# OSD.net
KiCad netlist of a schematic drawn in Altium Designer
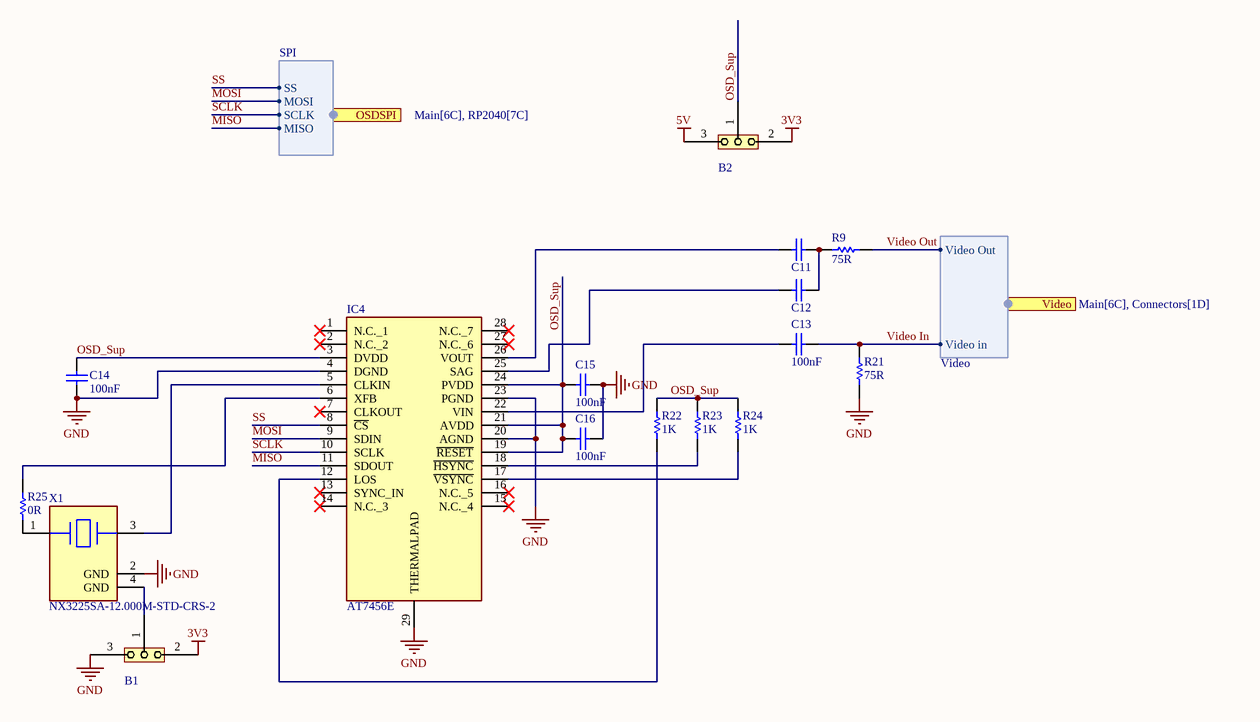
[diagram p0: OSD.SchDoc]

(export (version "E")
  (design (tool "Eeschema 10.0.6"))
  (components
    (comp (ref "B1")
      (value "0402 Solder Bridge")
      (footprint "Custom Components:0402 triple Solderbridge")
      (libsource (lib "Custom Components") (part "0402 Solder Bridge"))
    )
    (comp (ref "B2")
      (value "0402 Solder Bridge")
      (footprint "Custom Components:0402 triple Solderbridge")
      (libsource (lib "Custom Components") (part "0402 Solder Bridge"))
    )
    (comp (ref "C11")
      (value "10µF")
      (footprint "WCAP-CSGP_0603_L1.6W0.8H0.8_Reflow")
      (description "WCAP-CSGP Multilayer Ceramic Chip Capacitor, General Purpose, size 0603, X5R, 10µF, 25VDC")
      (fields
        (field (name "MANUFACTURER PART NUMBER") "885012106031")
        (field (name "MANUFACTURER") "Wurth Elektronik")
      )
      (libsource (lib "Altium_WCAP-CSGP (rev22f)") (part "885012106031"))
    )
    (comp (ref "C12")
      (value "10µF")
      (footprint "WCAP-CSGP_0603_L1.6W0.8H0.8_Reflow")
      (description "WCAP-CSGP Multilayer Ceramic Chip Capacitor, General Purpose, size 0603, X5R, 10µF, 25VDC")
      (fields
        (field (name "MANUFACTURER PART NUMBER") "885012106031")
        (field (name "MANUFACTURER") "Wurth Elektronik")
      )
      (libsource (lib "Altium_WCAP-CSGP (rev22f)") (part "885012106031"))
    )
    (comp (ref "C13")
      (value "100nF")
      (footprint "0402 cap")
      (libsource (lib "Custom Components") (part "Capacitor 0402 100nF"))
    )
    (comp (ref "C14")
      (value "100nF")
      (footprint "0402 cap")
      (libsource (lib "Custom Components") (part "Capacitor 0402 100nF"))
    )
    (comp (ref "C15")
      (value "100nF")
      (footprint "0402 cap")
      (libsource (lib "Custom Components") (part "Capacitor 0402 100nF"))
    )
    (comp (ref "C16")
      (value "100nF")
      (footprint "0402 cap")
      (libsource (lib "Custom Components") (part "Capacitor 0402 100nF"))
    )
    (comp (ref "IC4")
      (value "AT7456E")
      (footprint "SOP65P640X120-29N")
      (description "Integrated Circuit")
      (libsource (lib "Custom Components") (part "AT7456E"))
    )
    (comp (ref "R9")
      (value "75R")
      (footprint "Custom Components:0402 resistor")
      (libsource (lib "Custom Components") (part "Resistor 0402 1K"))
    )
    (comp (ref "R21")
      (value "75R")
      (footprint "Custom Components:0402 resistor")
      (libsource (lib "Custom Components") (part "Resistor 0402 1K"))
    )
    (comp (ref "R22")
      (value "1K")
      (footprint "Custom Components:0402 resistor")
      (libsource (lib "Custom Components") (part "Resistor 0402 1K"))
    )
    (comp (ref "R23")
      (value "1K")
      (footprint "Custom Components:0402 resistor")
      (libsource (lib "Custom Components") (part "Resistor 0402 1K"))
    )
    (comp (ref "R24")
      (value "1K")
      (footprint "Custom Components:0402 resistor")
      (libsource (lib "Custom Components") (part "Resistor 0402 1K"))
    )
    (comp (ref "R25")
      (value "0R")
      (footprint "Custom Components:0402 resistor")
      (libsource (lib "Custom Components") (part "Resistor 0402 1K"))
    )
    (comp (ref "X1")
      (value "NX3225SA-12.000M-STD-CRS-2")
      (footprint "FP-NX3225SA-MFG")
      (libsource (lib "Altium Content Vault") (part "48e526d86b7f2615d98721063c72f49"))
    )
  )
  (nets
    (net (code "3") (name "/MISO") (class "Default")
      (node (ref "IC4") (pin "11") (pinfunction "SDOUT_11") (pintype "passive"))
    )
    (net (code "4") (name "/MOSI") (class "Default")
      (node (ref "IC4") (pin "9") (pinfunction "SDIN_9") (pintype "passive"))
    )
    (net (code "5") (name "/OSD_Sup") (class "Default")
      (node (ref "B2") (pin "1") (pinfunction "1_1") (pintype "passive"))
      (node (ref "C14") (pin "2") (pinfunction "2_2") (pintype "passive"))
      (node (ref "C15") (pin "1") (pinfunction "1_1") (pintype "passive"))
      (node (ref "C16") (pin "1") (pinfunction "1_1") (pintype "passive"))
      (node (ref "IC4") (pin "19") (pinfunction "~{RESET}_19") (pintype "passive"))
      (node (ref "IC4") (pin "21") (pinfunction "AVDD_21") (pintype "passive"))
      (node (ref "IC4") (pin "24") (pinfunction "PVDD_24") (pintype "passive"))
      (node (ref "IC4") (pin "3") (pinfunction "DVDD_3") (pintype "passive"))
      (node (ref "R22") (pin "2") (pinfunction "2_2") (pintype "passive"))
      (node (ref "R23") (pin "2") (pinfunction "2_2") (pintype "passive"))
      (node (ref "R24") (pin "2") (pinfunction "2_2") (pintype "passive"))
    )
    (net (code "6") (name "/SCLK") (class "Default")
      (node (ref "IC4") (pin "10") (pinfunction "SCLK_10") (pintype "passive"))
    )
    (net (code "7") (name "/SS") (class "Default")
      (node (ref "IC4") (pin "8") (pinfunction "~{CS}_8") (pintype "passive"))
    )
    (net (code "8") (name "/Video In") (class "Default")
      (node (ref "C13") (pin "2") (pinfunction "2_2") (pintype "passive"))
      (node (ref "R21") (pin "1") (pinfunction "1_1") (pintype "passive"))
    )
    (net (code "9") (name "/Video Out") (class "Default")
      (node (ref "R9") (pin "1") (pinfunction "1_1") (pintype "passive"))
    )
    (net (code "12") (name "3V3") (class "Default")
      (node (ref "B1") (pin "2") (pinfunction "2_2") (pintype "passive"))
      (node (ref "B2") (pin "2") (pinfunction "2_2") (pintype "passive"))
    )
    (net (code "13") (name "5V") (class "Default")
      (node (ref "B2") (pin "3") (pinfunction "3_3") (pintype "passive"))
    )
    (net (code "14") (name "GND") (class "Default")
      (node (ref "B1") (pin "3") (pinfunction "3_3") (pintype "passive"))
      (node (ref "C14") (pin "1") (pinfunction "1_1") (pintype "passive"))
      (node (ref "C15") (pin "2") (pinfunction "2_2") (pintype "passive"))
      (node (ref "C16") (pin "2") (pinfunction "2_2") (pintype "passive"))
      (node (ref "IC4") (pin "20") (pinfunction "AGND_20") (pintype "passive"))
      (node (ref "IC4") (pin "23") (pinfunction "PGND_23") (pintype "passive"))
      (node (ref "IC4") (pin "29") (pinfunction "THERMALPAD_29") (pintype "passive"))
      (node (ref "IC4") (pin "4") (pinfunction "DGND_4") (pintype "passive"))
      (node (ref "R21") (pin "2") (pinfunction "2_2") (pintype "passive"))
      (node (ref "X1") (pin "2") (pinfunction "GND_2") (pintype "power_in"))
    )
    (net (code "15") (name "Net-(B1-Pad1)") (class "Default")
      (node (ref "B1") (pin "1") (pinfunction "1_1") (pintype "passive"))
      (node (ref "X1") (pin "4") (pinfunction "GND_4") (pintype "power_in"))
    )
    (net (code "16") (name "Net-(C11-Pad2)") (class "Default")
      (node (ref "C11") (pin "2") (pinfunction "2_2") (pintype "passive"))
      (node (ref "C12") (pin "2") (pinfunction "2_2") (pintype "passive"))
      (node (ref "R9") (pin "2") (pinfunction "2_2") (pintype "passive"))
    )
    (net (code "17") (name "Net-(IC4-CLKIN)") (class "Default")
      (node (ref "IC4") (pin "5") (pinfunction "CLKIN_5") (pintype "passive"))
      (node (ref "X1") (pin "3") (pinfunction "3_3") (pintype "passive"))
    )
    (net (code "18") (name "Net-(IC4-LOS)") (class "Default")
      (node (ref "IC4") (pin "12") (pinfunction "LOS_12") (pintype "passive"))
      (node (ref "R22") (pin "1") (pinfunction "1_1") (pintype "passive"))
    )
    (net (code "19") (name "Net-(IC4-SAG)") (class "Default")
      (node (ref "C12") (pin "1") (pinfunction "1_1") (pintype "passive"))
      (node (ref "IC4") (pin "25") (pinfunction "SAG_25") (pintype "passive"))
    )
    (net (code "20") (name "Net-(IC4-VIN)") (class "Default")
      (node (ref "C13") (pin "1") (pinfunction "1_1") (pintype "passive"))
      (node (ref "IC4") (pin "22") (pinfunction "VIN_22") (pintype "passive"))
    )
    (net (code "21") (name "Net-(IC4-VOUT)") (class "Default")
      (node (ref "C11") (pin "1") (pinfunction "1_1") (pintype "passive"))
      (node (ref "IC4") (pin "26") (pinfunction "VOUT_26") (pintype "passive"))
    )
    (net (code "22") (name "Net-(IC4-XFB)") (class "Default")
      (node (ref "IC4") (pin "6") (pinfunction "XFB_6") (pintype "passive"))
      (node (ref "R25") (pin "2") (pinfunction "2_2") (pintype "passive"))
    )
    (net (code "23") (name "Net-(IC4-~{HSYNC})") (class "Default")
      (node (ref "IC4") (pin "18") (pinfunction "~{HSYNC}_18") (pintype "passive"))
      (node (ref "R23") (pin "1") (pinfunction "1_1") (pintype "passive"))
    )
    (net (code "24") (name "Net-(IC4-~{VSYNC})") (class "Default")
      (node (ref "IC4") (pin "17") (pinfunction "~{VSYNC}_17") (pintype "passive"))
      (node (ref "R24") (pin "1") (pinfunction "1_1") (pintype "passive"))
    )
    (net (code "25") (name "Net-(R25-Pad1)") (class "Default")
      (node (ref "R25") (pin "1") (pinfunction "1_1") (pintype "passive"))
      (node (ref "X1") (pin "1") (pinfunction "1_1") (pintype "passive"))
    )
    (net (code "26") (name "unconnected-(IC4-CLKOUT-Pad7)") (class "Default")
      (node (ref "IC4") (pin "7") (pinfunction "CLKOUT_7") (pintype "passive+no_connect"))
    )
    (net (code "27") (name "unconnected-(IC4-N.C._1-Pad1)") (class "Default")
      (node (ref "IC4") (pin "1") (pinfunction "N.C._1_1") (pintype "passive+no_connect"))
    )
    (net (code "28") (name "unconnected-(IC4-N.C._2-Pad2)") (class "Default")
      (node (ref "IC4") (pin "2") (pinfunction "N.C._2_2") (pintype "passive+no_connect"))
    )
    (net (code "29") (name "unconnected-(IC4-N.C._3-Pad14)") (class "Default")
      (node (ref "IC4") (pin "14") (pinfunction "N.C._3_14") (pintype "passive+no_connect"))
    )
    (net (code "30") (name "unconnected-(IC4-N.C._4-Pad15)") (class "Default")
      (node (ref "IC4") (pin "15") (pinfunction "N.C._4_15") (pintype "passive+no_connect"))
    )
    (net (code "31") (name "unconnected-(IC4-N.C._5-Pad16)") (class "Default")
      (node (ref "IC4") (pin "16") (pinfunction "N.C._5_16") (pintype "passive+no_connect"))
    )
    (net (code "32") (name "unconnected-(IC4-N.C._6-Pad27)") (class "Default")
      (node (ref "IC4") (pin "27") (pinfunction "N.C._6_27") (pintype "passive+no_connect"))
    )
    (net (code "33") (name "unconnected-(IC4-N.C._7-Pad28)") (class "Default")
      (node (ref "IC4") (pin "28") (pinfunction "N.C._7_28") (pintype "passive+no_connect"))
    )
    (net (code "34") (name "unconnected-(IC4-SYNC_IN-Pad13)") (class "Default")
      (node (ref "IC4") (pin "13") (pinfunction "SYNC_IN_13") (pintype "passive+no_connect"))
    )
  )
)
